# GPS.net
KiCad netlist of a schematic drawn in Altium Designer
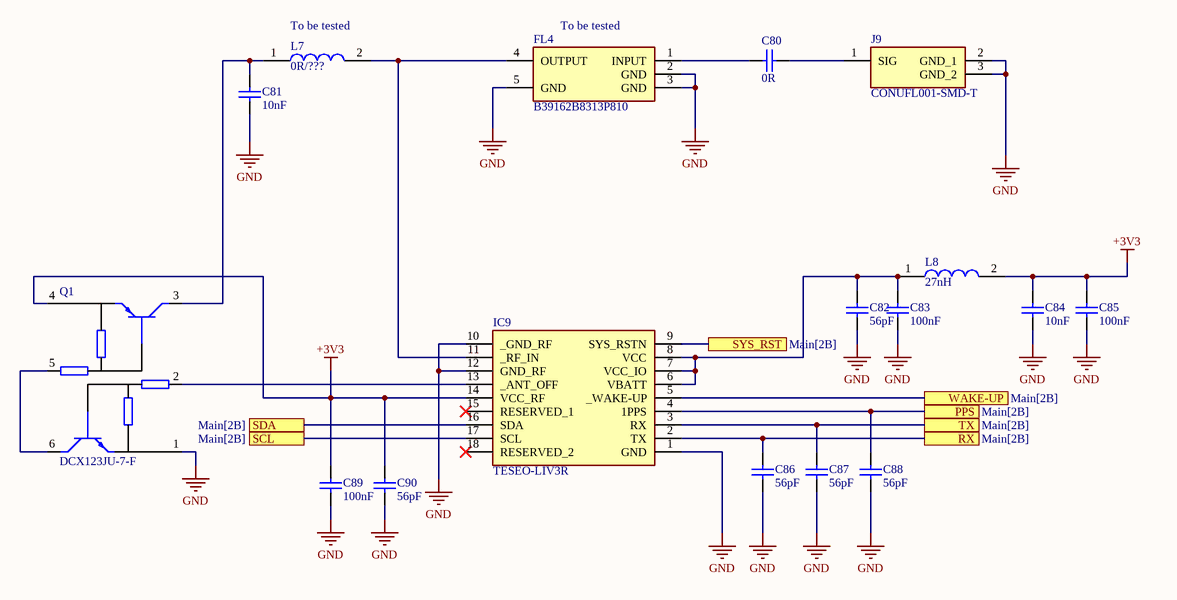
[diagram p0: GPS.SchDoc]

(export (version "E")
  (design (tool "Eeschema 10.0.6"))
  (components
    (comp (ref "C80")
      (value "0R")
      (footprint "CAP0402")
      (description "RF NP0")
      (fields (field (name "Comment") "Cap0402"))
      (libsource (lib "capacitorsSMD") (part "Cap0402"))
    )
    (comp (ref "C81")
      (value "10nF")
      (footprint "CAP0402")
      (description "RF NP0")
      (fields (field (name "VOLTAGE") "50V") (field (name "Comment") "Cap0402"))
      (libsource (lib "capacitorsSMD") (part "Cap0402"))
    )
    (comp (ref "C82")
      (value "56pF")
      (footprint "CAP0402")
      (fields (field (name "VOLTAGE") "50V") (field (name "Comment") "Cap0402"))
      (libsource (lib "capacitorsSMD") (part "Cap0402"))
    )
    (comp (ref "C83")
      (value "100nF")
      (footprint "CAP0402")
      (fields (field (name "VOLTAGE") "50V") (field (name "Comment") "Cap0402"))
      (libsource (lib "capacitorsSMD") (part "Cap0402"))
    )
    (comp (ref "C84")
      (value "10nF")
      (footprint "CAP0402")
      (fields (field (name "VOLTAGE") "50V") (field (name "Comment") "Cap0402"))
      (libsource (lib "capacitorsSMD") (part "Cap0402"))
    )
    (comp (ref "C85")
      (value "100nF")
      (footprint "CAP0402")
      (fields (field (name "VOLTAGE") "50V") (field (name "Comment") "Cap0402"))
      (libsource (lib "capacitorsSMD") (part "Cap0402"))
    )
    (comp (ref "C86")
      (value "56pF")
      (footprint "CAP0402")
      (fields (field (name "VOLTAGE") "50V") (field (name "Comment") "Cap0402"))
      (libsource (lib "capacitorsSMD") (part "Cap0402"))
    )
    (comp (ref "C87")
      (value "56pF")
      (footprint "CAP0402")
      (fields (field (name "VOLTAGE") "50V") (field (name "Comment") "Cap0402"))
      (libsource (lib "capacitorsSMD") (part "Cap0402"))
    )
    (comp (ref "C88")
      (value "56pF")
      (footprint "CAP0402")
      (fields (field (name "VOLTAGE") "50V") (field (name "Comment") "Cap0402"))
      (libsource (lib "capacitorsSMD") (part "Cap0402"))
    )
    (comp (ref "C89")
      (value "100nF")
      (footprint "CAP0402")
      (fields (field (name "VOLTAGE") "50V") (field (name "Comment") "Cap0402"))
      (libsource (lib "capacitorsSMD") (part "Cap0402"))
    )
    (comp (ref "C90")
      (value "56pF")
      (footprint "CAP0402")
      (fields (field (name "VOLTAGE") "50V") (field (name "Comment") "Cap0402"))
      (libsource (lib "capacitorsSMD") (part "Cap0402"))
    )
    (comp (ref "FL4")
      (value "B39162B8313P810")
      (footprint "SamacSys:B39162B8313P810")
      (description "Filter")
      (libsource (lib "SamacSys") (part "B39162B8313P810"))
    )
    (comp (ref "IC9")
      (value "TESEO-LIV3R")
      (footprint "SamacSys:TESEOLIV3R")
      (description "Integrated Circuit")
      (fields (field (name "MOUSER PART NUMBER") "511-TESEO-LIV3R"))
      (libsource (lib "*") (part "TESEO-LIV3R"))
    )
    (comp (ref "J9")
      (value "CONUFL001-SMD-T")
      (footprint "SamacSys:CONUFL001-SMD")
      (description "Connector")
      (fields (field (name "MOUSER PART NUMBER") "712-CONUFL001-SMD-T"))
      (libsource (lib "*") (part "CONUFL001-SMD-T"))
    )
    (comp (ref "L7")
      (value "0R/???")
      (footprint "SamacSys:INDC1005X55N")
      (description "Inductor")
      (fields (field (name "Comment") "LQG15HS27NJ02"))
      (libsource (lib "*") (part "LQG15HS27NJ02"))
    )
    (comp (ref "L8")
      (value "27nH")
      (footprint "SamacSys:INDC1005X55N")
      (description "Inductor")
      (fields (field (name "Comment") "LQG15HS27NJ02"))
      (libsource (lib "*") (part "LQG15HS27NJ02"))
    )
    (comp (ref "Q1")
      (value "DCX123JU-7-F")
      (footprint "SamacSys:SOT65P210X110-6N")
      (description "Transistor BJT PNP")
      (fields (field (name "MOUSER PART NUMBER") "621-DCX123JU-F"))
      (libsource (lib "SamacSys") (part "DCX123JU-7-F"))
    )
  )
  (nets
    (net (code "1") (name "+3V3") (class "Default")
      (node (ref "C84") (pin "2") (pinfunction "2_2") (pintype "passive"))
      (node (ref "C85") (pin "2") (pinfunction "2_2") (pintype "passive"))
      (node (ref "C89") (pin "2") (pinfunction "2_2") (pintype "passive"))
      (node (ref "C90") (pin "2") (pinfunction "2_2") (pintype "passive"))
      (node (ref "IC9") (pin "14") (pinfunction "VCC_RF_14") (pintype "passive"))
      (node (ref "L8") (pin "2") (pinfunction "2_2") (pintype "passive"))
      (node (ref "Q1") (pin "4") (pinfunction "E_4") (pintype "passive"))
    )
    (net (code "2") (name "/PPS") (class "Default")
      (node (ref "C88") (pin "2") (pinfunction "2_2") (pintype "passive"))
      (node (ref "IC9") (pin "4") (pinfunction "1PPS_4") (pintype "passive"))
    )
    (net (code "3") (name "/RX") (class "Default")
      (node (ref "C86") (pin "2") (pinfunction "2_2") (pintype "passive"))
      (node (ref "IC9") (pin "2") (pinfunction "TX_2") (pintype "passive"))
    )
    (net (code "4") (name "/SCL") (class "Default")
      (node (ref "IC9") (pin "17") (pinfunction "SCL_17") (pintype "passive"))
    )
    (net (code "5") (name "/SDA") (class "Default")
      (node (ref "IC9") (pin "16") (pinfunction "SDA_16") (pintype "passive"))
    )
    (net (code "6") (name "/SYS_RST") (class "Default")
      (node (ref "IC9") (pin "9") (pinfunction "SYS_RSTN_9") (pintype "passive"))
    )
    (net (code "7") (name "/TX") (class "Default")
      (node (ref "C87") (pin "2") (pinfunction "2_2") (pintype "passive"))
      (node (ref "IC9") (pin "3") (pinfunction "RX_3") (pintype "passive"))
    )
    (net (code "8") (name "/WAKE-UP") (class "Default")
      (node (ref "IC9") (pin "5") (pinfunction "_WAKE-UP_5") (pintype "passive"))
    )
    (net (code "9") (name "GND") (class "Default")
      (node (ref "C81") (pin "1") (pinfunction "1_1") (pintype "passive"))
      (node (ref "C82") (pin "1") (pinfunction "1_1") (pintype "passive"))
      (node (ref "C83") (pin "1") (pinfunction "1_1") (pintype "passive"))
      (node (ref "C84") (pin "1") (pinfunction "1_1") (pintype "passive"))
      (node (ref "C85") (pin "1") (pinfunction "1_1") (pintype "passive"))
      (node (ref "C86") (pin "1") (pinfunction "1_1") (pintype "passive"))
      (node (ref "C87") (pin "1") (pinfunction "1_1") (pintype "passive"))
      (node (ref "C88") (pin "1") (pinfunction "1_1") (pintype "passive"))
      (node (ref "C89") (pin "1") (pinfunction "1_1") (pintype "passive"))
      (node (ref "C90") (pin "1") (pinfunction "1_1") (pintype "passive"))
      (node (ref "FL4") (pin "2") (pinfunction "GND_2") (pintype "passive"))
      (node (ref "FL4") (pin "3") (pinfunction "GND_3") (pintype "passive"))
      (node (ref "FL4") (pin "5") (pinfunction "GND_5") (pintype "passive"))
      (node (ref "IC9") (pin "1") (pinfunction "GND_1") (pintype "passive"))
      (node (ref "IC9") (pin "10") (pinfunction "_GND_RF_10") (pintype "passive"))
      (node (ref "IC9") (pin "12") (pinfunction "GND_RF_12") (pintype "passive"))
      (node (ref "J9") (pin "2") (pinfunction "GND_1_2") (pintype "passive"))
      (node (ref "J9") (pin "3") (pinfunction "GND_2_3") (pintype "passive"))
      (node (ref "Q1") (pin "1") (pinfunction "E_1") (pintype "passive"))
    )
    (net (code "10") (name "Net-(C81-Pad2)") (class "Default")
      (node (ref "C81") (pin "2") (pinfunction "2_2") (pintype "passive"))
      (node (ref "L7") (pin "1") (pinfunction "1_1") (pintype "passive"))
      (node (ref "Q1") (pin "3") (pinfunction "C_3") (pintype "passive"))
    )
    (net (code "11") (name "Net-(FL4-INPUT)") (class "Default")
      (node (ref "C80") (pin "2") (pinfunction "2_2") (pintype "passive"))
      (node (ref "FL4") (pin "1") (pinfunction "INPUT_1") (pintype "passive"))
    )
    (net (code "12") (name "Net-(FL4-OUTPUT)") (class "Default")
      (node (ref "FL4") (pin "4") (pinfunction "OUTPUT_4") (pintype "passive"))
      (node (ref "IC9") (pin "11") (pinfunction "_RF_IN_11") (pintype "passive"))
      (node (ref "L7") (pin "2") (pinfunction "2_2") (pintype "passive"))
    )
    (net (code "13") (name "Net-(IC9-VBATT)") (class "Default")
      (node (ref "C82") (pin "2") (pinfunction "2_2") (pintype "passive"))
      (node (ref "C83") (pin "2") (pinfunction "2_2") (pintype "passive"))
      (node (ref "IC9") (pin "6") (pinfunction "VBATT_6") (pintype "passive"))
      (node (ref "IC9") (pin "7") (pinfunction "VCC_IO_7") (pintype "passive"))
      (node (ref "IC9") (pin "8") (pinfunction "VCC_8") (pintype "passive"))
      (node (ref "L8") (pin "1") (pinfunction "1_1") (pintype "passive"))
    )
    (net (code "14") (name "Net-(IC9-_ANT_OFF)") (class "Default")
      (node (ref "IC9") (pin "13") (pinfunction "_ANT_OFF_13") (pintype "passive"))
      (node (ref "Q1") (pin "2") (pinfunction "B_2") (pintype "passive"))
    )
    (net (code "15") (name "Net-(J9-SIG)") (class "Default")
      (node (ref "C80") (pin "1") (pinfunction "1_1") (pintype "passive"))
      (node (ref "J9") (pin "1") (pinfunction "SIG_1") (pintype "passive"))
    )
    (net (code "16") (name "Net-(Q1-B-Pad5)") (class "Default")
      (node (ref "Q1") (pin "5") (pinfunction "B_5") (pintype "passive"))
      (node (ref "Q1") (pin "6") (pinfunction "C_6") (pintype "passive"))
    )
    (net (code "17") (name "unconnected-(IC9-RESERVED_1-Pad15)") (class "Default")
      (node (ref "IC9") (pin "15") (pinfunction "RESERVED_1_15") (pintype "passive+no_connect"))
    )
    (net (code "18") (name "unconnected-(IC9-RESERVED_2-Pad18)") (class "Default")
      (node (ref "IC9") (pin "18") (pinfunction "RESERVED_2_18") (pintype "passive+no_connect"))
    )
  )
)
